# Fuzz.net
KiCad netlist of a schematic drawn in EAGLE
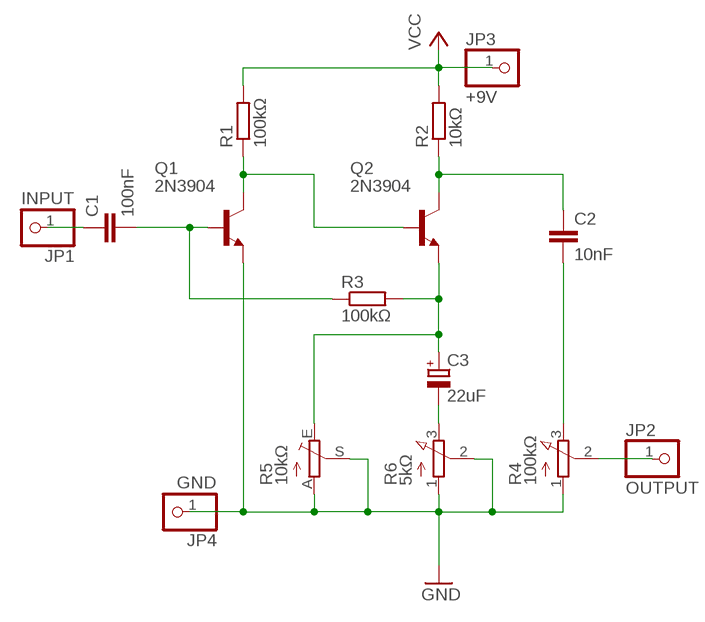
[diagram p0: schematic, sheet 1]

(export (version "E")
  (design (tool "Eeschema 10.0.6"))
  (components
    (comp (ref "C1")
      (value "100nF")
      (footprint "eagle-import:C050-024X044")
      (libsource (lib "eagle-import") (part "C-EU050-024X044"))
    )
    (comp (ref "C2")
      (value "10nF")
      (footprint "eagle-import:C050-024X044")
      (libsource (lib "eagle-import") (part "C-EU050-024X044"))
    )
    (comp (ref "C3")
      (value "22uF")
      (footprint "eagle-import:E5-5")
      (libsource (lib "eagle-import") (part "CPOL-EUE5-5"))
    )
    (comp (ref "JP1")
      (value "INPUT")
      (footprint "eagle-import:1X01")
      (libsource (lib "eagle-import") (part "PINHD-1X1"))
    )
    (comp (ref "JP2")
      (value "OUTPUT")
      (footprint "eagle-import:1X01")
      (libsource (lib "eagle-import") (part "PINHD-1X1"))
    )
    (comp (ref "JP3")
      (value "+9V")
      (footprint "eagle-import:1X01")
      (libsource (lib "eagle-import") (part "PINHD-1X1"))
    )
    (comp (ref "JP4")
      (value "GND")
      (footprint "eagle-import:1X01")
      (libsource (lib "eagle-import") (part "PINHD-1X1"))
    )
    (comp (ref "Q1")
      (value "2N3904")
      (footprint "eagle-import:TO92-EBC")
      (libsource (lib "eagle-import") (part "-NPN-TO92-EBC"))
    )
    (comp (ref "Q2")
      (value "2N3904")
      (footprint "eagle-import:TO92-EBC")
      (libsource (lib "eagle-import") (part "-NPN-TO92-EBC"))
    )
    (comp (ref "R1")
      (value "100kΩ")
      (footprint "eagle-import:0207_10")
      (libsource (lib "eagle-import") (part "R-EU_0207/10"))
    )
    (comp (ref "R2")
      (value "10kΩ")
      (footprint "eagle-import:0207_10")
      (libsource (lib "eagle-import") (part "R-EU_0207/10"))
    )
    (comp (ref "R3")
      (value "100kΩ")
      (footprint "eagle-import:0207_10")
      (libsource (lib "eagle-import") (part "R-EU_0207/10"))
    )
    (comp (ref "R4")
      (value "100kΩ")
      (footprint "eagle-import:3RP_1610N")
      (libsource (lib "eagle-import") (part "3RP/1610N"))
    )
    (comp (ref "R5")
      (value "10kΩ")
      (footprint "eagle-import:CA6V")
      (libsource (lib "eagle-import") (part "TRIM_EU-CA6V"))
    )
    (comp (ref "R6")
      (value "5kΩ")
      (footprint "eagle-import:3RP_1610N")
      (libsource (lib "eagle-import") (part "3RP/1610N"))
    )
  )
  (nets
    (net (code "1") (name "GND") (class "Default")
      (node (ref "JP4") (pin "1") (pinfunction "1_1") (pintype "passive"))
      (node (ref "Q1") (pin "E") (pinfunction "E_E") (pintype "passive"))
      (node (ref "R4") (pin "1") (pinfunction "A_1") (pintype "passive"))
      (node (ref "R5") (pin "A") (pinfunction "A_A") (pintype "passive"))
      (node (ref "R5") (pin "S") (pinfunction "S_S") (pintype "passive"))
      (node (ref "R6") (pin "1") (pinfunction "A_1") (pintype "passive"))
      (node (ref "R6") (pin "2") (pinfunction "S_2") (pintype "passive"))
    )
    (net (code "2") (name "Net-(C1-Pad1)") (class "Default")
      (node (ref "C1") (pin "1") (pinfunction "1_1") (pintype "passive"))
      (node (ref "JP1") (pin "1") (pinfunction "1_1") (pintype "passive"))
    )
    (net (code "3") (name "Net-(C1-Pad2)") (class "Default")
      (node (ref "C1") (pin "2") (pinfunction "2_2") (pintype "passive"))
      (node (ref "Q1") (pin "B") (pinfunction "B_B") (pintype "passive"))
      (node (ref "R3") (pin "1") (pinfunction "1_1") (pintype "passive"))
    )
    (net (code "4") (name "Net-(C2-Pad1)") (class "Default")
      (node (ref "C2") (pin "1") (pinfunction "1_1") (pintype "passive"))
      (node (ref "Q2") (pin "C") (pinfunction "C_C") (pintype "passive"))
      (node (ref "R2") (pin "1") (pinfunction "1_1") (pintype "passive"))
    )
    (net (code "5") (name "Net-(C3-Pad+)") (class "Default")
      (node (ref "C3") (pin "+") (pinfunction "+_+") (pintype "passive"))
      (node (ref "Q2") (pin "E") (pinfunction "E_E") (pintype "passive"))
      (node (ref "R3") (pin "2") (pinfunction "2_2") (pintype "passive"))
      (node (ref "R5") (pin "E") (pinfunction "E_E") (pintype "passive"))
    )
    (net (code "6") (name "Net-(Q1-PadC)") (class "Default")
      (node (ref "Q1") (pin "C") (pinfunction "C_C") (pintype "passive"))
      (node (ref "Q2") (pin "B") (pinfunction "B_B") (pintype "passive"))
      (node (ref "R1") (pin "1") (pinfunction "1_1") (pintype "passive"))
    )
    (net (code "7") (name "Net-(R4-E)") (class "Default")
      (node (ref "C2") (pin "2") (pinfunction "2_2") (pintype "passive"))
      (node (ref "R4") (pin "3") (pinfunction "E_3") (pintype "passive"))
    )
    (net (code "8") (name "Net-(R4-S)") (class "Default")
      (node (ref "JP2") (pin "1") (pinfunction "1_1") (pintype "passive"))
      (node (ref "R4") (pin "2") (pinfunction "S_2") (pintype "passive"))
    )
    (net (code "9") (name "Net-(R6-E)") (class "Default")
      (node (ref "C3") (pin "-") (pinfunction "-_-") (pintype "passive"))
      (node (ref "R6") (pin "3") (pinfunction "E_3") (pintype "passive"))
    )
    (net (code "10") (name "VCC") (class "Default")
      (node (ref "JP3") (pin "1") (pinfunction "1_1") (pintype "passive"))
      (node (ref "R1") (pin "2") (pinfunction "2_2") (pintype "passive"))
      (node (ref "R2") (pin "2") (pinfunction "2_2") (pintype "passive"))
    )
  )
)
